# Schematic_LED_SHIELD_DIGITAL.net
KiCad netlist of a schematic drawn in Altium Designer
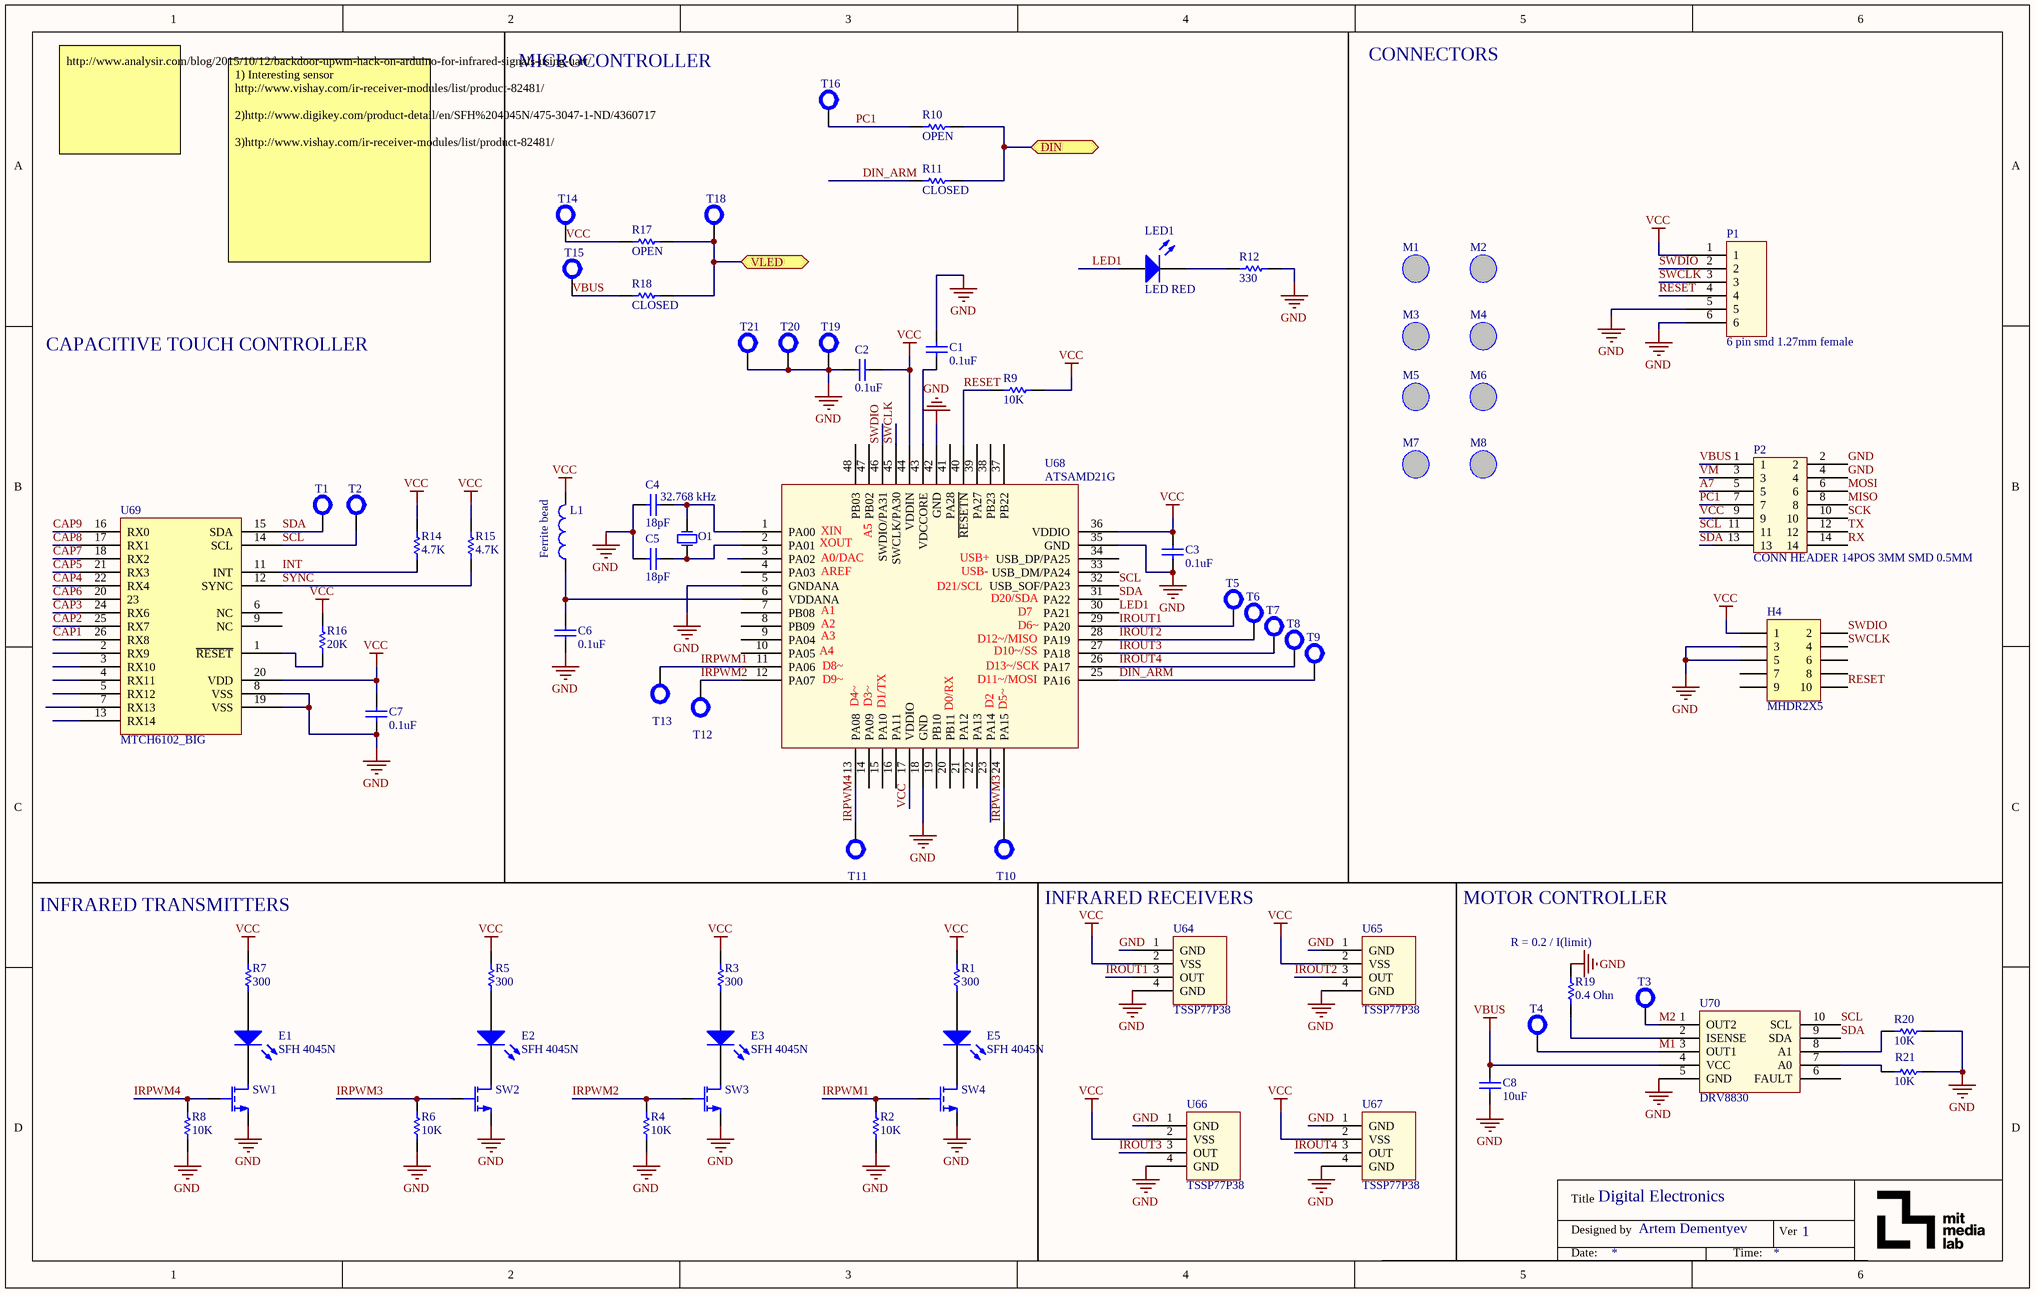
[diagram p0: Schematic_LED_SHIELD_DIGITAL.SchDoc]

(export (version "E")
  (design (tool "Eeschema 10.0.6"))
  (components
    (comp (ref "C1")
      (value "0.1uF")
      (footprint "0603W")
      (description "SMD Cap 1206")
      (libsource (lib "Artem_Library") (part "Capacitor"))
    )
    (comp (ref "C2")
      (value "0.1uF")
      (footprint "0603W")
      (description "SMD Cap 1206")
      (libsource (lib "Artem_Library") (part "Capacitor"))
    )
    (comp (ref "C3")
      (value "0.1uF")
      (footprint "0603W")
      (description "SMD Cap 1206")
      (libsource (lib "Artem_Library") (part "Capacitor"))
    )
    (comp (ref "C4")
      (value "18pF")
      (footprint "0603W")
      (description "SMD Cap 1206")
      (libsource (lib "Artem_Library") (part "Capacitor"))
    )
    (comp (ref "C5")
      (value "18pF")
      (footprint "0603W")
      (description "SMD Cap 1206")
      (libsource (lib "Artem_Library") (part "Capacitor"))
    )
    (comp (ref "C6")
      (value "0.1uF")
      (footprint "0603W")
      (description "SMD Cap 1206")
      (libsource (lib "Artem_Library") (part "Capacitor"))
    )
    (comp (ref "C7")
      (value "0.1uF")
      (footprint "0603W")
      (description "SMD Cap 1206")
      (libsource (lib "Artem_Library") (part "Capacitor"))
    )
    (comp (ref "C8")
      (value "10uF")
      (footprint "0603W")
      (description "SMD Cap 1206")
      (libsource (lib "Artem_Library") (part "Capacitor"))
    )
    (comp (ref "E1")
      (value "SFH 4045N")
      (footprint "SFH 4045N")
      (description "High Power Infrared Emitter (940 nm)")
      (fields (field (name "DIGIKEY PART NUMBER") "475-3047-1-ND"))
      (libsource (lib "Artem_Library") (part "SFH 4045N"))
    )
    (comp (ref "E2")
      (value "SFH 4045N")
      (footprint "SFH 4045N")
      (description "High Power Infrared Emitter (940 nm)")
      (fields (field (name "DIGIKEY PART NUMBER") "475-3047-1-ND"))
      (libsource (lib "Artem_Library") (part "SFH 4045N"))
    )
    (comp (ref "E3")
      (value "SFH 4045N")
      (footprint "SFH 4045N")
      (description "High Power Infrared Emitter (940 nm)")
      (fields (field (name "DIGIKEY PART NUMBER") "475-3047-1-ND"))
      (libsource (lib "Artem_Library") (part "SFH 4045N"))
    )
    (comp (ref "E5")
      (value "SFH 4045N")
      (footprint "SFH 4045N")
      (description "High Power Infrared Emitter (940 nm)")
      (fields (field (name "DIGIKEY PART NUMBER") "475-3047-1-ND"))
      (libsource (lib "Artem_Library") (part "SFH 4045N"))
    )
    (comp (ref "H4")
      (value "MHDR2X5")
      (footprint "MHDR2X5")
      (description "Header, 5-Pin, Dual row")
      (fields (field (name "PUBLISHER") "Altium Limited"))
      (libsource (lib "Miscellaneous Connectors") (part "MHDR2X5"))
    )
    (comp (ref "L1")
      (value "Ferrite bead")
      (footprint "0603W")
      (libsource (lib "Artem_Library") (part "INDUCTOR Low DCR"))
    )
    (comp (ref "LED1")
      (value "LED RED")
      (footprint "0603W")
      (description "LED SMD 1206/0603")
      (libsource (lib "Artem_Library") (part "LED"))
    )
    (comp (ref "M1")
      (value "Custom_magnet_holder")
      (footprint "3mm_magnet_holder")
      (libsource (lib "Artem_Library") (part "Custom_magnet_holder"))
    )
    (comp (ref "M2")
      (value "Custom_magnet_holder")
      (footprint "3mm_magnet_holder")
      (libsource (lib "Artem_Library") (part "Custom_magnet_holder"))
    )
    (comp (ref "M3")
      (value "Custom_magnet_holder")
      (footprint "3mm_magnet_holder")
      (libsource (lib "Artem_Library") (part "Custom_magnet_holder"))
    )
    (comp (ref "M4")
      (value "Custom_magnet_holder")
      (footprint "3mm_magnet_holder")
      (libsource (lib "Artem_Library") (part "Custom_magnet_holder"))
    )
    (comp (ref "M5")
      (value "Custom_magnet_holder")
      (footprint "3mm_magnet_holder")
      (libsource (lib "Artem_Library") (part "Custom_magnet_holder"))
    )
    (comp (ref "M6")
      (value "Custom_magnet_holder")
      (footprint "3mm_magnet_holder")
      (libsource (lib "Artem_Library") (part "Custom_magnet_holder"))
    )
    (comp (ref "M7")
      (value "Custom_magnet_holder")
      (footprint "3mm_magnet_holder")
      (libsource (lib "Artem_Library") (part "Custom_magnet_holder"))
    )
    (comp (ref "M8")
      (value "Custom_magnet_holder")
      (footprint "3mm_magnet_holder")
      (libsource (lib "Artem_Library") (part "Custom_magnet_holder"))
    )
    (comp (ref "O1")
      (value "32.768 kHz")
      (footprint "32.768 Crystal")
      (libsource (lib "Artem_Library") (part "32.768 Crystal"))
    )
    (comp (ref "P1")
      (value "6 pin smd 1.27mm female")
      (footprint "6pos 1.27mm")
      (libsource (lib "Artem_Library") (part "6 pin smd 1.27mm female"))
    )
    (comp (ref "P2")
      (value "CONN HEADER 14POS 3MM SMD 0.5MM")
      (footprint "DF12 14Pos Female")
      (fields (field (name "DIGIKEY PART NUMBER") "H11701TR-ND"))
      (libsource (lib "Artem_Library") (part "CONN HEADER 14POS 3MM SMD 0.5MM"))
    )
    (comp (ref "R1") (value "300") (footprint "0603W") (libsource (lib "Artem_Library") (part "Resistor")))
    (comp (ref "R2") (value "10K") (footprint "0603W") (libsource (lib "Artem_Library") (part "Resistor")))
    (comp (ref "R3") (value "300") (footprint "0603W") (libsource (lib "Artem_Library") (part "Resistor")))
    (comp (ref "R4") (value "10K") (footprint "0603W") (libsource (lib "Artem_Library") (part "Resistor")))
    (comp (ref "R5") (value "300") (footprint "0603W") (libsource (lib "Artem_Library") (part "Resistor")))
    (comp (ref "R6") (value "10K") (footprint "0603W") (libsource (lib "Artem_Library") (part "Resistor")))
    (comp (ref "R7") (value "300") (footprint "0603W") (libsource (lib "Artem_Library") (part "Resistor")))
    (comp (ref "R8") (value "10K") (footprint "0603W") (libsource (lib "Artem_Library") (part "Resistor")))
    (comp (ref "R9") (value "10K") (footprint "0603W") (libsource (lib "Artem_Library") (part "Resistor")))
    (comp (ref "R10") (value "OPEN") (footprint "0603W") (libsource (lib "Artem_Library") (part "Resistor")))
    (comp (ref "R11")
      (value "CLOSED")
      (footprint "0603W")
      (libsource (lib "Artem_Library") (part "Resistor"))
    )
    (comp (ref "R12") (value "330") (footprint "0603W") (libsource (lib "Artem_Library") (part "Resistor")))
    (comp (ref "R14") (value "4.7K") (footprint "0603W") (libsource (lib "Artem_Library") (part "Resistor")))
    (comp (ref "R15") (value "4.7K") (footprint "0603W") (libsource (lib "Artem_Library") (part "Resistor")))
    (comp (ref "R16") (value "20K") (footprint "0603W") (libsource (lib "Artem_Library") (part "Resistor")))
    (comp (ref "R17") (value "OPEN") (footprint "0603W") (libsource (lib "Artem_Library") (part "Resistor")))
    (comp (ref "R18")
      (value "CLOSED")
      (footprint "0603W")
      (libsource (lib "Artem_Library") (part "Resistor"))
    )
    (comp (ref "R19")
      (value "0.4 Ohn")
      (footprint "0603W")
      (libsource (lib "Artem_Library") (part "Resistor"))
    )
    (comp (ref "R20") (value "10K") (footprint "0603W") (libsource (lib "Artem_Library") (part "Resistor")))
    (comp (ref "R21") (value "10K") (footprint "0603W") (libsource (lib "Artem_Library") (part "Resistor")))
    (comp (ref "SW1")
      (value "MOSFET N CHANNEL")
      (footprint "SOT323")
      (fields (field (name "DIGIKEY PART NUMBER") "568-5987-1-ND"))
      (libsource (lib "Artem_Library") (part "MOSFET N CHANNEL"))
    )
    (comp (ref "SW2")
      (value "MOSFET N CHANNEL")
      (footprint "SOT323")
      (fields (field (name "DIGIKEY PART NUMBER") "568-5987-1-ND"))
      (libsource (lib "Artem_Library") (part "MOSFET N CHANNEL"))
    )
    (comp (ref "SW3")
      (value "MOSFET N CHANNEL")
      (footprint "SOT323")
      (fields (field (name "DIGIKEY PART NUMBER") "568-5987-1-ND"))
      (libsource (lib "Artem_Library") (part "MOSFET N CHANNEL"))
    )
    (comp (ref "SW4")
      (value "MOSFET N CHANNEL")
      (footprint "SOT323")
      (fields (field (name "DIGIKEY PART NUMBER") "568-5987-1-ND"))
      (libsource (lib "Artem_Library") (part "MOSFET N CHANNEL"))
    )
    (comp (ref "T1")
      (value "Test point small")
      (footprint "TEST POINT SMD SUPER SMALL")
      (libsource (lib "Artem_Library") (part "Test point small"))
    )
    (comp (ref "T2")
      (value "Test point small")
      (footprint "TEST POINT SMD SUPER SMALL")
      (libsource (lib "Artem_Library") (part "Test point small"))
    )
    (comp (ref "T3")
      (value "Test point small")
      (footprint "TEST POINT SMD SUPER SMALL")
      (libsource (lib "Artem_Library") (part "Test point small"))
    )
    (comp (ref "T4")
      (value "Test point small")
      (footprint "TEST POINT SMD SUPER SMALL")
      (libsource (lib "Artem_Library") (part "Test point small"))
    )
    (comp (ref "T5")
      (value "Test point small")
      (footprint "TEST POINT SMD SUPER SMALL")
      (libsource (lib "Artem_Library") (part "Test point small"))
    )
    (comp (ref "T6")
      (value "Test point small")
      (footprint "TEST POINT SMD SUPER SMALL")
      (libsource (lib "Artem_Library") (part "Test point small"))
    )
    (comp (ref "T7")
      (value "Test point small")
      (footprint "TEST POINT SMD SUPER SMALL")
      (libsource (lib "Artem_Library") (part "Test point small"))
    )
    (comp (ref "T8")
      (value "Test point small")
      (footprint "TEST POINT SMD SUPER SMALL")
      (libsource (lib "Artem_Library") (part "Test point small"))
    )
    (comp (ref "T9")
      (value "Test point small")
      (footprint "TEST POINT SMD SUPER SMALL")
      (libsource (lib "Artem_Library") (part "Test point small"))
    )
    (comp (ref "T10")
      (value "Test point small")
      (footprint "TEST POINT SMD SUPER SMALL")
      (libsource (lib "Artem_Library") (part "Test point small"))
    )
    (comp (ref "T11")
      (value "Test point small")
      (footprint "TEST POINT SMD SUPER SMALL")
      (libsource (lib "Artem_Library") (part "Test point small"))
    )
    (comp (ref "T12")
      (value "Test point small")
      (footprint "TEST POINT SMD SUPER SMALL")
      (libsource (lib "Artem_Library") (part "Test point small"))
    )
    (comp (ref "T13")
      (value "Test point small")
      (footprint "TEST POINT SMD SUPER SMALL")
      (libsource (lib "Artem_Library") (part "Test point small"))
    )
    (comp (ref "T14")
      (value "Test point small")
      (footprint "TEST POINT SMD SUPER SMALL")
      (libsource (lib "Artem_Library") (part "Test point small"))
    )
    (comp (ref "T15")
      (value "Test point small")
      (footprint "TEST POINT SMD SUPER SMALL")
      (libsource (lib "Artem_Library") (part "Test point small"))
    )
    (comp (ref "T16")
      (value "Test point small")
      (footprint "TEST POINT SMD SUPER SMALL")
      (libsource (lib "Artem_Library") (part "Test point small"))
    )
    (comp (ref "T18")
      (value "Test point small")
      (footprint "TEST POINT SMD SUPER SMALL")
      (libsource (lib "Artem_Library") (part "Test point small"))
    )
    (comp (ref "T19")
      (value "Test point small")
      (footprint "TEST POINT SMD SUPER SMALL")
      (libsource (lib "Artem_Library") (part "Test point small"))
    )
    (comp (ref "T20")
      (value "Test point small")
      (footprint "TEST POINT SMD SUPER SMALL")
      (libsource (lib "Artem_Library") (part "Test point small"))
    )
    (comp (ref "T21")
      (value "Test point small")
      (footprint "TEST POINT SMD SUPER SMALL")
      (libsource (lib "Artem_Library") (part "Test point small"))
    )
    (comp (ref "U64")
      (value "TSSP77P38")
      (footprint "TSSP77P38")
      (description "IR Detector for Mid Range Proximity Sensor")
      (fields (field (name "DIGIKEY PART NUMBER") "TSSP77P38TCT-ND"))
      (libsource (lib "Artem_Library") (part "TSSP77P38"))
    )
    (comp (ref "U65")
      (value "TSSP77P38")
      (footprint "TSSP77P38")
      (description "IR Detector for Mid Range Proximity Sensor")
      (fields (field (name "DIGIKEY PART NUMBER") "TSSP77P38TCT-ND"))
      (libsource (lib "Artem_Library") (part "TSSP77P38"))
    )
    (comp (ref "U66")
      (value "TSSP77P38")
      (footprint "TSSP77P38")
      (description "IR Detector for Mid Range Proximity Sensor")
      (fields (field (name "DIGIKEY PART NUMBER") "TSSP77P38TCT-ND"))
      (libsource (lib "Artem_Library") (part "TSSP77P38"))
    )
    (comp (ref "U67")
      (value "TSSP77P38")
      (footprint "TSSP77P38")
      (description "IR Detector for Mid Range Proximity Sensor")
      (fields (field (name "DIGIKEY PART NUMBER") "TSSP77P38TCT-ND"))
      (libsource (lib "Artem_Library") (part "TSSP77P38"))
    )
    (comp (ref "U68")
      (value "ATSAMD21G")
      (footprint "TQFN48")
      (description "IC MCU 32BIT 256KB FLASH 48TQFP")
      (fields (field (name "DIGIKEY PART NUMBER") "ATSAMD21G18A-AUTCT-ND"))
      (libsource (lib "Artem_Library") (part "ATSAMD21G"))
    )
    (comp (ref "U69")
      (value "MTCH6102_BIG")
      (footprint "SS28")
      (libsource (lib "Artem_Library") (part "MTCH6102_BIG"))
    )
    (comp (ref "U70")
      (value "DRV8830")
      (footprint "MSOP10_TI_POWERPAD")
      (description "Low-Voltage Motor Driver With Serial Interface")
      (fields (field (name "DIGIKEY PART NUMBER") "296-28165-1-ND"))
      (libsource (lib "Artem_Library") (part "DRV8830"))
    )
  )
  (nets
    (net (code "1") (name "/A7") (class "Default")
      (node (ref "P2") (pin "5") (pinfunction "5_5") (pintype "passive"))
    )
    (net (code "2") (name "/CAP1") (class "Default")
      (node (ref "U69") (pin "26") (pinfunction "RX8_26") (pintype "passive"))
    )
    (net (code "3") (name "/CAP2") (class "Default")
      (node (ref "U69") (pin "25") (pinfunction "RX7_25") (pintype "passive"))
    )
    (net (code "4") (name "/CAP3") (class "Default")
      (node (ref "U69") (pin "24") (pinfunction "RX6_24") (pintype "passive"))
    )
    (net (code "5") (name "/CAP4") (class "Default")
      (node (ref "U69") (pin "22") (pinfunction "RX4_22") (pintype "passive"))
    )
    (net (code "6") (name "/CAP5") (class "Default")
      (node (ref "U69") (pin "21") (pinfunction "RX3_21") (pintype "passive"))
    )
    (net (code "7") (name "/CAP6") (class "Default")
      (node (ref "U69") (pin "20") (pinfunction "23_20") (pintype "passive"))
    )
    (net (code "8") (name "/CAP7") (class "Default")
      (node (ref "U69") (pin "18") (pinfunction "RX2_18") (pintype "passive"))
    )
    (net (code "9") (name "/CAP8") (class "Default")
      (node (ref "U69") (pin "17") (pinfunction "RX1_17") (pintype "passive"))
    )
    (net (code "10") (name "/CAP9") (class "Default")
      (node (ref "U69") (pin "16") (pinfunction "RX0_16") (pintype "passive"))
    )
    (net (code "11") (name "/DIN") (class "Default")
      (node (ref "R10") (pin "1") (pinfunction "1_1") (pintype "passive"))
      (node (ref "R11") (pin "1") (pinfunction "1_1") (pintype "passive"))
    )
    (net (code "12") (name "/DIN_ARM") (class "Default")
      (node (ref "R11") (pin "2") (pinfunction "2_2") (pintype "passive"))
      (node (ref "T9") (pin "0") (pinfunction "0_0") (pintype "passive"))
      (node (ref "U68") (pin "25") (pinfunction "PA16_25") (pintype "passive"))
    )
    (net (code "13") (name "/INT") (class "Default")
      (node (ref "R14") (pin "1") (pinfunction "1_1") (pintype "passive"))
      (node (ref "U69") (pin "11") (pinfunction "INT_11") (pintype "passive"))
    )
    (net (code "14") (name "/IROUT1") (class "Default")
      (node (ref "T5") (pin "0") (pinfunction "0_0") (pintype "passive"))
      (node (ref "U64") (pin "3") (pinfunction "OUT_3") (pintype "passive"))
      (node (ref "U68") (pin "29") (pinfunction "PA20_29") (pintype "passive"))
    )
    (net (code "15") (name "/IROUT2") (class "Default")
      (node (ref "T6") (pin "0") (pinfunction "0_0") (pintype "passive"))
      (node (ref "U65") (pin "3") (pinfunction "OUT_3") (pintype "passive"))
      (node (ref "U68") (pin "28") (pinfunction "PA19_28") (pintype "passive"))
    )
    (net (code "16") (name "/IROUT3") (class "Default")
      (node (ref "T7") (pin "0") (pinfunction "0_0") (pintype "passive"))
      (node (ref "U66") (pin "3") (pinfunction "OUT_3") (pintype "passive"))
      (node (ref "U68") (pin "27") (pinfunction "PA18_27") (pintype "passive"))
    )
    (net (code "17") (name "/IROUT4") (class "Default")
      (node (ref "T8") (pin "0") (pinfunction "0_0") (pintype "passive"))
      (node (ref "U67") (pin "3") (pinfunction "OUT_3") (pintype "passive"))
      (node (ref "U68") (pin "26") (pinfunction "PA17_26") (pintype "passive"))
    )
    (net (code "18") (name "/IRPWM1") (class "Default")
      (node (ref "R2") (pin "1") (pinfunction "1_1") (pintype "passive"))
      (node (ref "SW4") (pin "1") (pinfunction "G_1") (pintype "passive"))
      (node (ref "T13") (pin "0") (pinfunction "0_0") (pintype "passive"))
      (node (ref "U68") (pin "11") (pinfunction "PA06_11") (pintype "passive"))
    )
    (net (code "19") (name "/IRPWM2") (class "Default")
      (node (ref "R4") (pin "1") (pinfunction "1_1") (pintype "passive"))
      (node (ref "SW3") (pin "1") (pinfunction "G_1") (pintype "passive"))
      (node (ref "T12") (pin "0") (pinfunction "0_0") (pintype "passive"))
      (node (ref "U68") (pin "12") (pinfunction "PA07_12") (pintype "passive"))
    )
    (net (code "20") (name "/IRPWM3") (class "Default")
      (node (ref "R6") (pin "1") (pinfunction "1_1") (pintype "passive"))
      (node (ref "SW2") (pin "1") (pinfunction "G_1") (pintype "passive"))
      (node (ref "T10") (pin "0") (pinfunction "0_0") (pintype "passive"))
      (node (ref "U68") (pin "24") (pinfunction "PA15_24") (pintype "passive"))
    )
    (net (code "21") (name "/IRPWM4") (class "Default")
      (node (ref "R8") (pin "1") (pinfunction "1_1") (pintype "passive"))
      (node (ref "SW1") (pin "1") (pinfunction "G_1") (pintype "passive"))
      (node (ref "T11") (pin "0") (pinfunction "0_0") (pintype "passive"))
      (node (ref "U68") (pin "13") (pinfunction "PA08_13") (pintype "passive"))
    )
    (net (code "22") (name "/LED1") (class "Default")
      (node (ref "LED1") (pin "1") (pinfunction "A_1") (pintype "passive"))
      (node (ref "U68") (pin "30") (pinfunction "PA21_30") (pintype "passive"))
    )
    (net (code "23") (name "/M1") (class "Default")
      (node (ref "T4") (pin "0") (pinfunction "0_0") (pintype "passive"))
      (node (ref "U70") (pin "3") (pinfunction "OUT1_3") (pintype "passive"))
    )
    (net (code "24") (name "/M2") (class "Default")
      (node (ref "T3") (pin "0") (pinfunction "0_0") (pintype "passive"))
      (node (ref "U70") (pin "1") (pinfunction "OUT2_1") (pintype "passive"))
    )
    (net (code "25") (name "/MISO") (class "Default")
      (node (ref "P2") (pin "8") (pinfunction "8_8") (pintype "passive"))
    )
    (net (code "26") (name "/MOSI") (class "Default")
      (node (ref "P2") (pin "6") (pinfunction "6_6") (pintype "passive"))
    )
    (net (code "27") (name "/PC1") (class "Default")
      (node (ref "P2") (pin "7") (pinfunction "7_7") (pintype "passive"))
      (node (ref "R10") (pin "2") (pinfunction "2_2") (pintype "passive"))
      (node (ref "T16") (pin "0") (pinfunction "0_0") (pintype "passive"))
    )
    (net (code "28") (name "/RESET") (class "Default")
      (node (ref "H4") (pin "10") (pinfunction "10_10") (pintype "passive"))
      (node (ref "P1") (pin "4") (pinfunction "4_4") (pintype "passive"))
      (node (ref "R9") (pin "2") (pinfunction "2_2") (pintype "passive"))
      (node (ref "U68") (pin "40") (pinfunction "~{RESETN}_40") (pintype "passive"))
    )
    (net (code "29") (name "/RX") (class "Default")
      (node (ref "P2") (pin "14") (pinfunction "14_14") (pintype "passive"))
    )
    (net (code "30") (name "/SCK") (class "Default")
      (node (ref "P2") (pin "10") (pinfunction "10_10") (pintype "passive"))
    )
    (net (code "31") (name "/SCL") (class "Default")
      (node (ref "P2") (pin "11") (pinfunction "11_11") (pintype "passive"))
      (node (ref "T2") (pin "0") (pinfunction "0_0") (pintype "passive"))
      (node (ref "U68") (pin "32") (pinfunction "USB_SOF/PA23_32") (pintype "passive"))
      (node (ref "U69") (pin "14") (pinfunction "SCL_14") (pintype "passive"))
      (node (ref "U70") (pin "10") (pinfunction "SCL_10") (pintype "passive"))
    )
    (net (code "32") (name "/SDA") (class "Default")
      (node (ref "P2") (pin "13") (pinfunction "13_13") (pintype "passive"))
      (node (ref "T1") (pin "0") (pinfunction "0_0") (pintype "passive"))
      (node (ref "U68") (pin "31") (pinfunction "PA22_31") (pintype "passive"))
      (node (ref "U69") (pin "15") (pinfunction "SDA_15") (pintype "passive"))
      (node (ref "U70") (pin "9") (pinfunction "SDA_9") (pintype "passive"))
    )
    (net (code "33") (name "/SWCLK") (class "Default")
      (node (ref "H4") (pin "4") (pinfunction "4_4") (pintype "passive"))
      (node (ref "P1") (pin "3") (pinfunction "3_3") (pintype "passive"))
      (node (ref "U68") (pin "45") (pinfunction "SWCLK/PA30_45") (pintype "passive"))
    )
    (net (code "34") (name "/SWDIO") (class "Default")
      (node (ref "H4") (pin "2") (pinfunction "2_2") (pintype "passive"))
      (node (ref "P1") (pin "2") (pinfunction "2_2") (pintype "passive"))
      (node (ref "U68") (pin "46") (pinfunction "SWDIO/PA31_46") (pintype "passive"))
    )
    (net (code "35") (name "/SYNC") (class "Default")
      (node (ref "R15") (pin "1") (pinfunction "1_1") (pintype "passive"))
      (node (ref "U69") (pin "12") (pinfunction "SYNC_12") (pintype "passive"))
    )
    (net (code "36") (name "/TX") (class "Default")
      (node (ref "P2") (pin "12") (pinfunction "12_12") (pintype "passive"))
    )
    (net (code "37") (name "/VLED") (class "Default")
      (node (ref "R17") (pin "1") (pinfunction "1_1") (pintype "passive"))
      (node (ref "R18") (pin "1") (pinfunction "1_1") (pintype "passive"))
      (node (ref "T18") (pin "0") (pinfunction "0_0") (pintype "passive"))
    )
    (net (code "38") (name "/VM") (class "Default")
      (node (ref "P2") (pin "3") (pinfunction "3_3") (pintype "passive"))
    )
    (net (code "39") (name "GND") (class "Default")
      (node (ref "C1") (pin "2") (pinfunction "2_2") (pintype "passive"))
      (node (ref "C2") (pin "2") (pinfunction "2_2") (pintype "passive"))
      (node (ref "C3") (pin "1") (pinfunction "1_1") (pintype "passive"))
      (node (ref "C4") (pin "2") (pinfunction "2_2") (pintype "passive"))
      (node (ref "C5") (pin "2") (pinfunction "2_2") (pintype "passive"))
      (node (ref "C6") (pin "1") (pinfunction "1_1") (pintype "passive"))
      (node (ref "C7") (pin "1") (pinfunction "1_1") (pintype "passive"))
      (node (ref "C8") (pin "1") (pinfunction "1_1") (pintype "passive"))
      (node (ref "H4") (pin "3") (pinfunction "3_3") (pintype "passive"))
      (node (ref "H4") (pin "5") (pinfunction "5_5") (pintype "passive"))
      (node (ref "P1") (pin "5") (pinfunction "5_5") (pintype "passive"))
      (node (ref "P1") (pin "6") (pinfunction "6_6") (pintype "passive"))
      (node (ref "P2") (pin "2") (pinfunction "2_2") (pintype "passive"))
      (node (ref "P2") (pin "4") (pinfunction "4_4") (pintype "passive"))
      (node (ref "R12") (pin "1") (pinfunction "1_1") (pintype "passive"))
      (node (ref "R19") (pin "1") (pinfunction "1_1") (pintype "passive"))
      (node (ref "R2") (pin "2") (pinfunction "2_2") (pintype "passive"))
      (node (ref "R20") (pin "2") (pinfunction "2_2") (pintype "passive"))
      (node (ref "R21") (pin "2") (pinfunction "2_2") (pintype "passive"))
      (node (ref "R4") (pin "2") (pinfunction "2_2") (pintype "passive"))
      (node (ref "R6") (pin "2") (pinfunction "2_2") (pintype "passive"))
      (node (ref "R8") (pin "2") (pinfunction "2_2") (pintype "passive"))
      (node (ref "SW1") (pin "2") (pinfunction "S_2") (pintype "passive"))
      (node (ref "SW2") (pin "2") (pinfunction "S_2") (pintype "passive"))
      (node (ref "SW3") (pin "2") (pinfunction "S_2") (pintype "passive"))
      (node (ref "SW4") (pin "2") (pinfunction "S_2") (pintype "passive"))
      (node (ref "T19") (pin "0") (pinfunction "0_0") (pintype "passive"))
      (node (ref "T20") (pin "0") (pinfunction "0_0") (pintype "passive"))
      (node (ref "T21") (pin "0") (pinfunction "0_0") (pintype "passive"))
      (node (ref "U64") (pin "1") (pinfunction "GND_1") (pintype "passive"))
      (node (ref "U64") (pin "4") (pinfunction "GND_4") (pintype "passive"))
      (node (ref "U65") (pin "1") (pinfunction "GND_1") (pintype "passive"))
      (node (ref "U65") (pin "4") (pinfunction "GND_4") (pintype "passive"))
      (node (ref "U66") (pin "1") (pinfunction "GND_1") (pintype "passive"))
      (node (ref "U66") (pin "4") (pinfunction "GND_4") (pintype "passive"))
      (node (ref "U67") (pin "1") (pinfunction "GND_1") (pintype "passive"))
      (node (ref "U67") (pin "4") (pinfunction "GND_4") (pintype "passive"))
      (node (ref "U68") (pin "18") (pinfunction "GND_18") (pintype "passive"))
      (node (ref "U68") (pin "35") (pinfunction "GND_35") (pintype "passive"))
      (node (ref "U68") (pin "42") (pinfunction "GND_42") (pintype "passive"))
      (node (ref "U68") (pin "5") (pinfunction "GNDANA_5") (pintype "passive"))
      (node (ref "U69") (pin "19") (pinfunction "VSS_19") (pintype "passive"))
      (node (ref "U69") (pin "8") (pinfunction "VSS_8") (pintype "passive"))
      (node (ref "U70") (pin "5") (pinfunction "GND_5") (pintype "passive"))
    )
    (net (code "40") (name "Net-(E1-Anode)") (class "Default")
      (node (ref "E1") (pin "2") (pinfunction "Anode_2") (pintype "passive"))
      (node (ref "R7") (pin "2") (pinfunction "2_2") (pintype "passive"))
    )
    (net (code "41") (name "Net-(E1-Cathode)") (class "Default")
      (node (ref "E1") (pin "1") (pinfunction "Cathode_1") (pintype "passive"))
      (node (ref "SW1") (pin "3") (pinfunction "D_3") (pintype "passive"))
    )
    (net (code "42") (name "Net-(E2-Anode)") (class "Default")
      (node (ref "E2") (pin "2") (pinfunction "Anode_2") (pintype "passive"))
      (node (ref "R5") (pin "2") (pinfunction "2_2") (pintype "passive"))
    )
    (net (code "43") (name "Net-(E2-Cathode)") (class "Default")
      (node (ref "E2") (pin "1") (pinfunction "Cathode_1") (pintype "passive"))
      (node (ref "SW2") (pin "3") (pinfunction "D_3") (pintype "passive"))
    )
    (net (code "44") (name "Net-(E3-Anode)") (class "Default")
      (node (ref "E3") (pin "2") (pinfunction "Anode_2") (pintype "passive"))
      (node (ref "R3") (pin "2") (pinfunction "2_2") (pintype "passive"))
    )
    (net (code "45") (name "Net-(E3-Cathode)") (class "Default")
      (node (ref "E3") (pin "1") (pinfunction "Cathode_1") (pintype "passive"))
      (node (ref "SW3") (pin "3") (pinfunction "D_3") (pintype "passive"))
    )
    (net (code "46") (name "Net-(E5-Anode)") (class "Default")
      (node (ref "E5") (pin "2") (pinfunction "Anode_2") (pintype "passive"))
      (node (ref "R1") (pin "2") (pinfunction "2_2") (pintype "passive"))
    )
    (net (code "47") (name "Net-(E5-Cathode)") (class "Default")
      (node (ref "E5") (pin "1") (pinfunction "Cathode_1") (pintype "passive"))
      (node (ref "SW4") (pin "3") (pinfunction "D_3") (pintype "passive"))
    )
    (net (code "48") (name "Net-(LED1-K)") (class "Default")
      (node (ref "LED1") (pin "2") (pinfunction "K_2") (pintype "passive"))
      (node (ref "R12") (pin "2") (pinfunction "2_2") (pintype "passive"))
    )
    (net (code "49") (name "Net-(U68-PA00)") (class "Default")
      (node (ref "C4") (pin "1") (pinfunction "1_1") (pintype "passive"))
      (node (ref "O1") (pin "1") (pinfunction "1_1") (pintype "passive"))
      (node (ref "U68") (pin "1") (pinfunction "PA00_1") (pintype "passive"))
    )
    (net (code "50") (name "Net-(U68-PA01)") (class "Default")
      (node (ref "C5") (pin "1") (pinfunction "1_1") (pintype "passive"))
      (node (ref "O1") (pin "2") (pinfunction "2_2") (pintype "passive"))
      (node (ref "U68") (pin "2") (pinfunction "PA01_2") (pintype "passive"))
    )
    (net (code "51") (name "Net-(U68-VDCCORE)") (class "Default")
      (node (ref "C1") (pin "1") (pinfunction "1_1") (pintype "passive"))
      (node (ref "U68") (pin "43") (pinfunction "VDCCORE_43") (pintype "passive"))
    )
    (net (code "52") (name "Net-(U68-VDDANA)") (class "Default")
      (node (ref "C6") (pin "2") (pinfunction "2_2") (pintype "passive"))
      (node (ref "L1") (pin "1") (pinfunction "1_1") (pintype "passive"))
      (node (ref "U68") (pin "6") (pinfunction "VDDANA_6") (pintype "passive"))
    )
    (net (code "53") (name "Net-(U69-~{RESET})") (class "Default")
      (node (ref "R16") (pin "2") (pinfunction "2_2") (pintype "passive"))
      (node (ref "U69") (pin "1") (pinfunction "~{RESET}_1") (pintype "passive"))
    )
    (net (code "54") (name "Net-(U70-A0)") (class "Default")
      (node (ref "R21") (pin "1") (pinfunction "1_1") (pintype "passive"))
      (node (ref "U70") (pin "7") (pinfunction "A0_7") (pintype "passive"))
    )
    (net (code "55") (name "Net-(U70-A1)") (class "Default")
      (node (ref "R20") (pin "1") (pinfunction "1_1") (pintype "passive"))
      (node (ref "U70") (pin "8") (pinfunction "A1_8") (pintype "passive"))
    )
    (net (code "56") (name "Net-(U70-ISENSE)") (class "Default")
      (node (ref "R19") (pin "2") (pinfunction "2_2") (pintype "passive"))
      (node (ref "U70") (pin "2") (pinfunction "ISENSE_2") (pintype "passive"))
    )
    (net (code "57") (name "VBUS") (class "Default")
      (node (ref "C8") (pin "2") (pinfunction "2_2") (pintype "passive"))
      (node (ref "P2") (pin "1") (pinfunction "1_1") (pintype "passive"))
      (node (ref "R18") (pin "2") (pinfunction "2_2") (pintype "passive"))
      (node (ref "T15") (pin "0") (pinfunction "0_0") (pintype "passive"))
      (node (ref "U70") (pin "4") (pinfunction "VCC_4") (pintype "passive"))
    )
    (net (code "58") (name "VCC") (class "Default")
      (node (ref "C2") (pin "1") (pinfunction "1_1") (pintype "passive"))
      (node (ref "C3") (pin "2") (pinfunction "2_2") (pintype "passive"))
      (node (ref "C7") (pin "2") (pinfunction "2_2") (pintype "passive"))
      (node (ref "H4") (pin "1") (pinfunction "1_1") (pintype "passive"))
      (node (ref "L1") (pin "2") (pinfunction "2_2") (pintype "passive"))
      (node (ref "P1") (pin "1") (pinfunction "1_1") (pintype "passive"))
      (node (ref "P2") (pin "9") (pinfunction "9_9") (pintype "passive"))
      (node (ref "R1") (pin "1") (pinfunction "1_1") (pintype "passive"))
      (node (ref "R14") (pin "2") (pinfunction "2_2") (pintype "passive"))
      (node (ref "R15") (pin "2") (pinfunction "2_2") (pintype "passive"))
      (node (ref "R16") (pin "1") (pinfunction "1_1") (pintype "passive"))
      (node (ref "R17") (pin "2") (pinfunction "2_2") (pintype "passive"))
      (node (ref "R3") (pin "1") (pinfunction "1_1") (pintype "passive"))
      (node (ref "R5") (pin "1") (pinfunction "1_1") (pintype "passive"))
      (node (ref "R7") (pin "1") (pinfunction "1_1") (pintype "passive"))
      (node (ref "R9") (pin "1") (pinfunction "1_1") (pintype "passive"))
      (node (ref "T14") (pin "0") (pinfunction "0_0") (pintype "passive"))
      (node (ref "U64") (pin "2") (pinfunction "VSS_2") (pintype "passive"))
      (node (ref "U65") (pin "2") (pinfunction "VSS_2") (pintype "passive"))
      (node (ref "U66") (pin "2") (pinfunction "VSS_2") (pintype "passive"))
      (node (ref "U67") (pin "2") (pinfunction "VSS_2") (pintype "passive"))
      (node (ref "U68") (pin "17") (pinfunction "VDDIO_17") (pintype "passive"))
      (node (ref "U68") (pin "36") (pinfunction "VDDIO_36") (pintype "passive"))
      (node (ref "U68") (pin "44") (pinfunction "VDDIN_44") (pintype "passive"))
      (node (ref "U69") (pin "20") (pinfunction "VDD_20") (pintype "passive"))
    )
    (net (code "59") (name "unconnected-(H4-Pad6)") (class "Default")
      (node (ref "H4") (pin "6") (pinfunction "6_6") (pintype "passive"))
    )
    (net (code "60") (name "unconnected-(H4-Pad7)") (class "Default")
      (node (ref "H4") (pin "7") (pinfunction "7_7") (pintype "passive"))
    )
    (net (code "61") (name "unconnected-(H4-Pad8)") (class "Default")
      (node (ref "H4") (pin "8") (pinfunction "8_8") (pintype "passive"))
    )
    (net (code "62") (name "unconnected-(H4-Pad9)") (class "Default")
      (node (ref "H4") (pin "9") (pinfunction "9_9") (pintype "passive"))
    )
    (net (code "63") (name "unconnected-(U68-PA02-Pad3)") (class "Default")
      (node (ref "U68") (pin "3") (pinfunction "PA02_3") (pintype "passive"))
    )
    (net (code "64") (name "unconnected-(U68-PA03-Pad4)") (class "Default")
      (node (ref "U68") (pin "4") (pinfunction "PA03_4") (pintype "passive"))
    )
    (net (code "65") (name "unconnected-(U68-PA04-Pad9)") (class "Default")
      (node (ref "U68") (pin "9") (pinfunction "PA04_9") (pintype "passive"))
    )
    (net (code "66") (name "unconnected-(U68-PA05-Pad10)") (class "Default")
      (node (ref "U68") (pin "10") (pinfunction "PA05_10") (pintype "passive"))
    )
    (net (code "67") (name "unconnected-(U68-PA09-Pad14)") (class "Default")
      (node (ref "U68") (pin "14") (pinfunction "PA09_14") (pintype "passive"))
    )
    (net (code "68") (name "unconnected-(U68-PA10-Pad15)") (class "Default")
      (node (ref "U68") (pin "15") (pinfunction "PA10_15") (pintype "passive"))
    )
    (net (code "69") (name "unconnected-(U68-PA11-Pad16)") (class "Default")
      (node (ref "U68") (pin "16") (pinfunction "PA11_16") (pintype "passive"))
    )
    (net (code "70") (name "unconnected-(U68-PA12-Pad21)") (class "Default")
      (node (ref "U68") (pin "21") (pinfunction "PA12_21") (pintype "passive"))
    )
    (net (code "71") (name "unconnected-(U68-PA13-Pad22)") (class "Default")
      (node (ref "U68") (pin "22") (pinfunction "PA13_22") (pintype "passive"))
    )
    (net (code "72") (name "unconnected-(U68-PA14-Pad23)") (class "Default")
      (node (ref "U68") (pin "23") (pinfunction "PA14_23") (pintype "passive"))
    )
    (net (code "73") (name "unconnected-(U68-PA27-Pad39)") (class "Default")
      (node (ref "U68") (pin "39") (pinfunction "PA27_39") (pintype "passive"))
    )
    (net (code "74") (name "unconnected-(U68-PA28-Pad41)") (class "Default")
      (node (ref "U68") (pin "41") (pinfunction "PA28_41") (pintype "passive"))
    )
    (net (code "75") (name "unconnected-(U68-PB02-Pad47)") (class "Default")
      (node (ref "U68") (pin "47") (pinfunction "PB02_47") (pintype "passive"))
    )
    (net (code "76") (name "unconnected-(U68-PB03-Pad48)") (class "Default")
      (node (ref "U68") (pin "48") (pinfunction "PB03_48") (pintype "passive"))
    )
    (net (code "77") (name "unconnected-(U68-PB08-Pad7)") (class "Default")
      (node (ref "U68") (pin "7") (pinfunction "PB08_7") (pintype "passive"))
    )
    (net (code "78") (name "unconnected-(U68-PB09-Pad8)") (class "Default")
      (node (ref "U68") (pin "8") (pinfunction "PB09_8") (pintype "passive"))
    )
    (net (code "79") (name "unconnected-(U68-PB10-Pad19)") (class "Default")
      (node (ref "U68") (pin "19") (pinfunction "PB10_19") (pintype "passive"))
    )
    (net (code "80") (name "unconnected-(U68-PB11-Pad20)") (class "Default")
      (node (ref "U68") (pin "20") (pinfunction "PB11_20") (pintype "passive"))
    )
    (net (code "81") (name "unconnected-(U68-PB22-Pad37)") (class "Default")
      (node (ref "U68") (pin "37") (pinfunction "PB22_37") (pintype "passive"))
    )
    (net (code "82") (name "unconnected-(U68-PB23-Pad38)") (class "Default")
      (node (ref "U68") (pin "38") (pinfunction "PB23_38") (pintype "passive"))
    )
    (net (code "83") (name "unconnected-(U68-USB_DM{slash}PA24-Pad33)") (class "Default")
      (node (ref "U68") (pin "33") (pinfunction "USB_DM/PA24_33") (pintype "passive"))
    )
    (net (code "84") (name "unconnected-(U68-USB_DP{slash}PA25-Pad34)") (class "Default")
      (node (ref "U68") (pin "34") (pinfunction "USB_DP/PA25_34") (pintype "passive"))
    )
    (net (code "85") (name "unconnected-(U69-NC-Pad6)") (class "Default")
      (node (ref "U69") (pin "6") (pinfunction "NC_6") (pintype "passive"))
    )
    (net (code "86") (name "unconnected-(U69-NC-Pad9)") (class "Default")
      (node (ref "U69") (pin "9") (pinfunction "NC_9") (pintype "passive"))
    )
    (net (code "87") (name "unconnected-(U69-RX9-Pad2)") (class "Default")
      (node (ref "U69") (pin "2") (pinfunction "RX9_2") (pintype "passive"))
    )
    (net (code "88") (name "unconnected-(U69-RX10-Pad3)") (class "Default")
      (node (ref "U69") (pin "3") (pinfunction "RX10_3") (pintype "passive"))
    )
    (net (code "89") (name "unconnected-(U69-RX11-Pad4)") (class "Default")
      (node (ref "U69") (pin "4") (pinfunction "RX11_4") (pintype "passive"))
    )
    (net (code "90") (name "unconnected-(U69-RX12-Pad5)") (class "Default")
      (node (ref "U69") (pin "5") (pinfunction "RX12_5") (pintype "passive"))
    )
    (net (code "91") (name "unconnected-(U69-RX13-Pad7)") (class "Default")
      (node (ref "U69") (pin "7") (pinfunction "RX13_7") (pintype "passive"))
    )
    (net (code "92") (name "unconnected-(U69-RX14-Pad13)") (class "Default")
      (node (ref "U69") (pin "13") (pinfunction "RX14_13") (pintype "passive"))
    )
    (net (code "93") (name "unconnected-(U70-FAULT-Pad6)") (class "Default")
      (node (ref "U70") (pin "6") (pinfunction "FAULT_6") (pintype "passive"))
    )
  )
)
